# HES_Board_Rev1.net
KiCad netlist of a schematic drawn in EAGLE
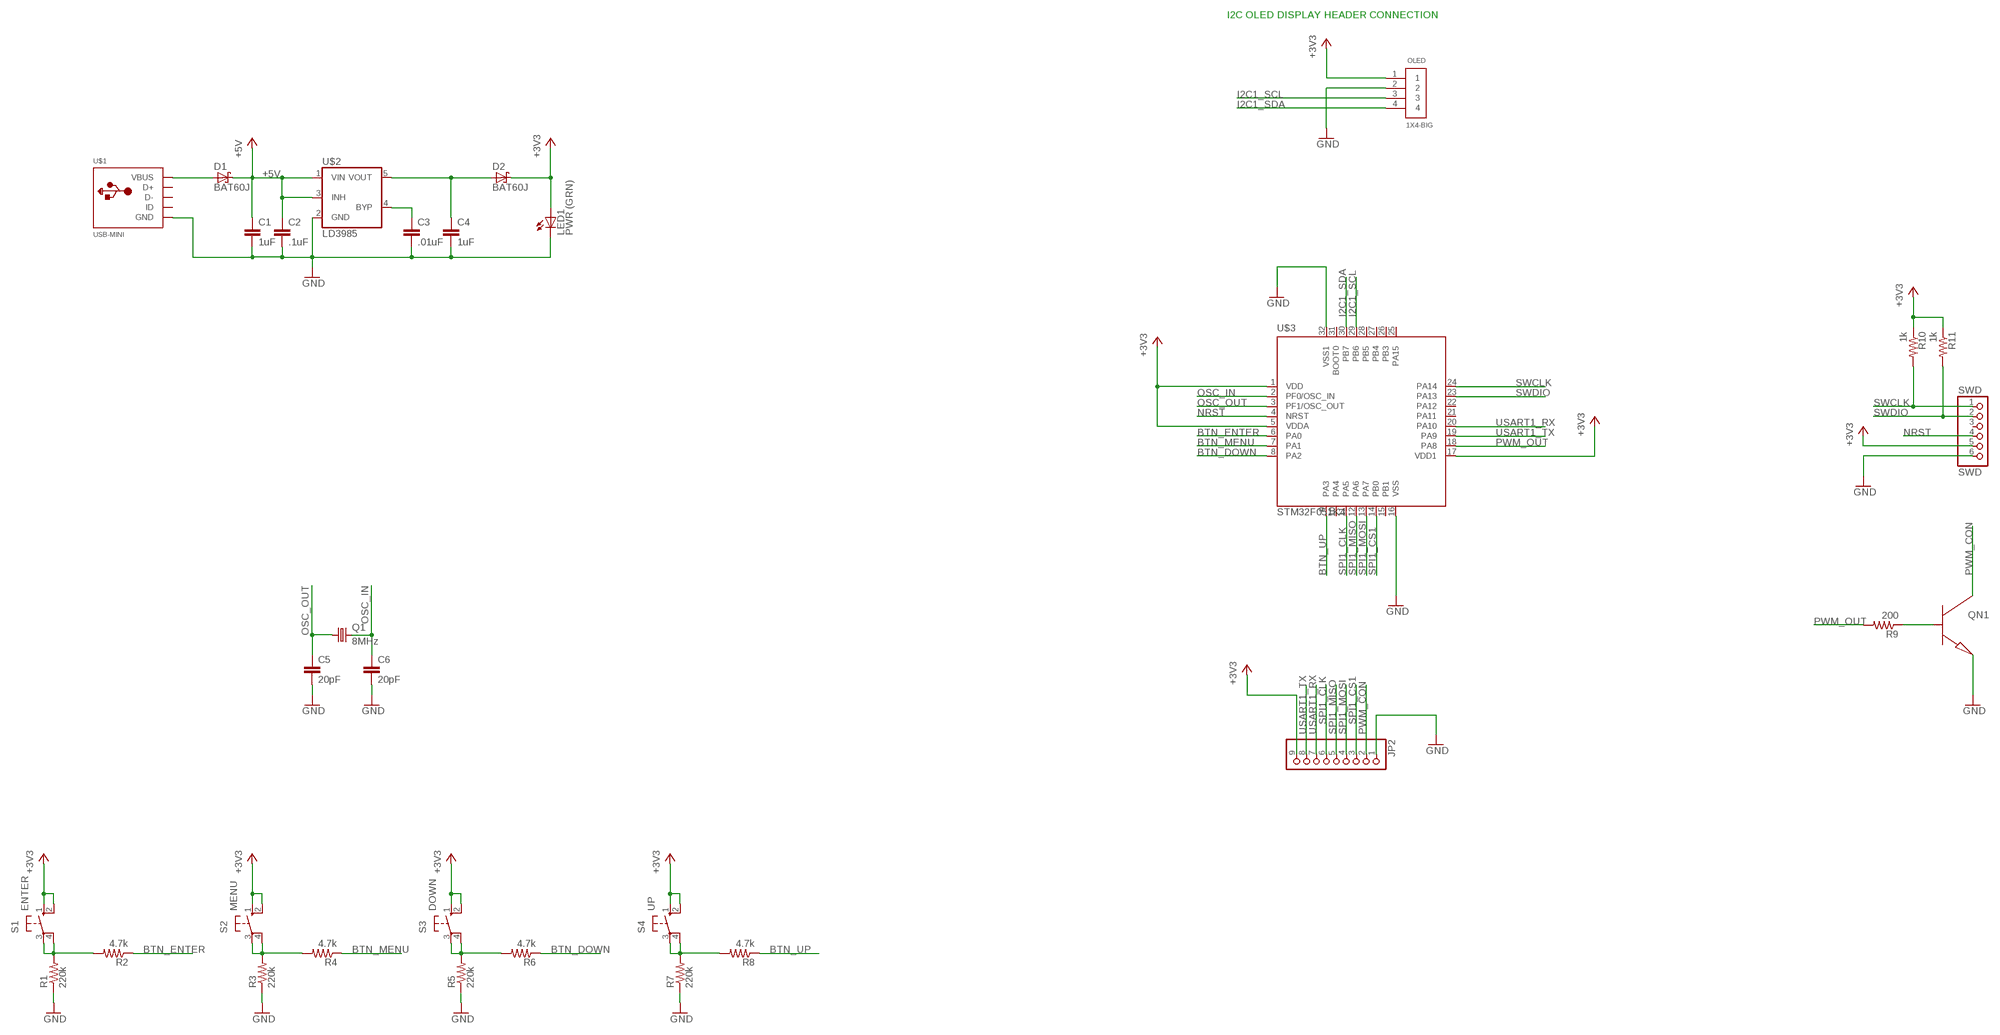
[diagram p0: schematic, sheet 1]

(export (version "E")
  (design (tool "Eeschema 10.0.6"))
  (components
    (comp (ref "C1")
      (value "1uF")
      (footprint "eagle-import:C0805")
      (libsource (lib "eagle-import") (part "C-EUC0805"))
    )
    (comp (ref "C2")
      (value ".1uF")
      (footprint "eagle-import:C0805")
      (libsource (lib "eagle-import") (part "C-EUC0805"))
    )
    (comp (ref "C3")
      (value ".01uF")
      (footprint "eagle-import:C0805")
      (libsource (lib "eagle-import") (part "C-EUC0805"))
    )
    (comp (ref "C4")
      (value "1uF")
      (footprint "eagle-import:C0805")
      (libsource (lib "eagle-import") (part "C-EUC0805"))
    )
    (comp (ref "C5")
      (value "20pF")
      (footprint "eagle-import:C0805")
      (libsource (lib "eagle-import") (part "C-EUC0805"))
    )
    (comp (ref "C6")
      (value "20pF")
      (footprint "eagle-import:C0805")
      (libsource (lib "eagle-import") (part "C-EUC0805"))
    )
    (comp (ref "D1")
      (value "BAT60J")
      (footprint "eagle-import:SOD323_ST")
      (libsource (lib "eagle-import") (part "BAT60J"))
    )
    (comp (ref "D2")
      (value "BAT60J")
      (footprint "eagle-import:SOD323_ST")
      (libsource (lib "eagle-import") (part "BAT60J"))
    )
    (comp (ref "JP2")
      (value "PINHD-1X9")
      (footprint "eagle-import:1X09-BIG")
      (libsource (lib "eagle-import") (part "PINHD-1X9"))
    )
    (comp (ref "LED1")
      (value "PWR (GRN)")
      (footprint "eagle-import:CHIP-LED0805")
      (libsource (lib "eagle-import") (part "LEDCHIP-LED0805"))
    )
    (comp (ref "OLED")
      (value "1X4-BIG")
      (footprint "eagle-import:1X04-BIG")
      (libsource (lib "eagle-import") (part "1X4-BIG"))
    )
    (comp (ref "Q1")
      (value "8MHz")
      (footprint "eagle-import:HC49_S")
      (libsource (lib "eagle-import") (part "CRYSTALHC49S"))
    )
    (comp (ref "QN1")
      (value "NPN")
      (footprint "eagle-import:SOT23")
      (libsource (lib "eagle-import") (part "NPN"))
    )
    (comp (ref "R1")
      (value "220k")
      (footprint "eagle-import:R0805")
      (libsource (lib "eagle-import") (part "R-US_R0805"))
    )
    (comp (ref "R2")
      (value "4.7k")
      (footprint "eagle-import:R0805")
      (libsource (lib "eagle-import") (part "R-US_R0805"))
    )
    (comp (ref "R3")
      (value "220k")
      (footprint "eagle-import:R0805")
      (libsource (lib "eagle-import") (part "R-US_R0805"))
    )
    (comp (ref "R4")
      (value "4.7k")
      (footprint "eagle-import:R0805")
      (libsource (lib "eagle-import") (part "R-US_R0805"))
    )
    (comp (ref "R5")
      (value "220k")
      (footprint "eagle-import:R0805")
      (libsource (lib "eagle-import") (part "R-US_R0805"))
    )
    (comp (ref "R6")
      (value "4.7k")
      (footprint "eagle-import:R0805")
      (libsource (lib "eagle-import") (part "R-US_R0805"))
    )
    (comp (ref "R7")
      (value "220k")
      (footprint "eagle-import:R0805")
      (libsource (lib "eagle-import") (part "R-US_R0805"))
    )
    (comp (ref "R8")
      (value "4.7k")
      (footprint "eagle-import:R0805")
      (libsource (lib "eagle-import") (part "R-US_R0805"))
    )
    (comp (ref "R9")
      (value "200")
      (footprint "eagle-import:R0805")
      (libsource (lib "eagle-import") (part "R-US_R0805"))
    )
    (comp (ref "R10")
      (value "1k")
      (footprint "eagle-import:R0805")
      (libsource (lib "eagle-import") (part "R-US_R0805"))
    )
    (comp (ref "R11")
      (value "1k")
      (footprint "eagle-import:R0805")
      (libsource (lib "eagle-import") (part "R-US_R0805"))
    )
    (comp (ref "S1")
      (value "ENTER")
      (footprint "eagle-import:B3F-10XX")
      (fields (field (name "MPN") "B3F-1000"))
      (libsource (lib "eagle-import") (part "10-XX"))
    )
    (comp (ref "S2")
      (value "MENU")
      (footprint "eagle-import:B3F-10XX")
      (fields (field (name "MPN") "B3F-1000"))
      (libsource (lib "eagle-import") (part "10-XX"))
    )
    (comp (ref "S3")
      (value "DOWN")
      (footprint "eagle-import:B3F-10XX")
      (fields (field (name "MPN") "B3F-1000"))
      (libsource (lib "eagle-import") (part "10-XX"))
    )
    (comp (ref "S4")
      (value "UP")
      (footprint "eagle-import:B3F-10XX")
      (fields (field (name "MPN") "B3F-1000"))
      (libsource (lib "eagle-import") (part "10-XX"))
    )
    (comp (ref "SWD")
      (value "SWD")
      (footprint "eagle-import:1X06-BIG")
      (libsource (lib "eagle-import") (part "PINHD-1X6B"))
    )
    (comp (ref "U$1")
      (value "USB-MINI")
      (footprint "eagle-import:USB-MINI")
      (libsource (lib "eagle-import") (part "USB-MINI"))
    )
    (comp (ref "U$2")
      (value "LD3985")
      (footprint "eagle-import:SOT23-5L")
      (libsource (lib "eagle-import") (part "LD3985"))
    )
    (comp (ref "U$3")
      (value "STM32F051K4")
      (footprint "eagle-import:LQFP32-7X7")
      (libsource (lib "eagle-import") (part "STM32F051K4"))
    )
  )
  (nets
    (net (code "1") (name "+3V3") (class "Default")
      (node (ref "D2") (pin "C") (pinfunction "C_C") (pintype "passive"))
      (node (ref "JP2") (pin "9") (pinfunction "9_9") (pintype "passive"))
      (node (ref "LED1") (pin "A") (pinfunction "A_A") (pintype "passive"))
      (node (ref "OLED") (pin "1") (pinfunction "1_1") (pintype "bidirectional"))
      (node (ref "R10") (pin "1") (pinfunction "1_1") (pintype "passive"))
      (node (ref "R11") (pin "1") (pinfunction "1_1") (pintype "passive"))
      (node (ref "S1") (pin "1") (pinfunction "S_1") (pintype "passive"))
      (node (ref "S1") (pin "2") (pinfunction "S1_2") (pintype "passive"))
      (node (ref "S2") (pin "1") (pinfunction "S_1") (pintype "passive"))
      (node (ref "S2") (pin "2") (pinfunction "S1_2") (pintype "passive"))
      (node (ref "S3") (pin "1") (pinfunction "S_1") (pintype "passive"))
      (node (ref "S3") (pin "2") (pinfunction "S1_2") (pintype "passive"))
      (node (ref "S4") (pin "1") (pinfunction "S_1") (pintype "passive"))
      (node (ref "S4") (pin "2") (pinfunction "S1_2") (pintype "passive"))
      (node (ref "SWD") (pin "5") (pinfunction "5_5") (pintype "passive"))
      (node (ref "U$3") (pin "1") (pinfunction "VDD_1") (pintype "power_in"))
      (node (ref "U$3") (pin "17") (pinfunction "VDD1_17") (pintype "power_in"))
      (node (ref "U$3") (pin "5") (pinfunction "VDDA_5") (pintype "power_in"))
    )
    (net (code "2") (name "+5V") (class "Default")
      (node (ref "C1") (pin "1") (pinfunction "1_1") (pintype "passive"))
      (node (ref "C2") (pin "1") (pinfunction "1_1") (pintype "passive"))
      (node (ref "D1") (pin "C") (pinfunction "C_C") (pintype "passive"))
      (node (ref "U$2") (pin "1") (pinfunction "VIN_1") (pintype "input"))
      (node (ref "U$2") (pin "3") (pinfunction "INH_3") (pintype "input"))
    )
    (net (code "3") (name "/BTN_DOWN") (class "Default")
      (node (ref "R6") (pin "1") (pinfunction "1_1") (pintype "passive"))
      (node (ref "U$3") (pin "8") (pinfunction "PA2_8") (pintype "bidirectional"))
    )
    (net (code "4") (name "/BTN_ENTER") (class "Default")
      (node (ref "R2") (pin "1") (pinfunction "1_1") (pintype "passive"))
      (node (ref "U$3") (pin "6") (pinfunction "PA0_6") (pintype "bidirectional"))
    )
    (net (code "5") (name "/BTN_MENU") (class "Default")
      (node (ref "R4") (pin "1") (pinfunction "1_1") (pintype "passive"))
      (node (ref "U$3") (pin "7") (pinfunction "PA1_7") (pintype "bidirectional"))
    )
    (net (code "6") (name "/BTN_UP") (class "Default")
      (node (ref "R8") (pin "1") (pinfunction "1_1") (pintype "passive"))
      (node (ref "U$3") (pin "9") (pinfunction "PA3_9") (pintype "bidirectional"))
    )
    (net (code "7") (name "/I2C1_SCL") (class "Default")
      (node (ref "OLED") (pin "3") (pinfunction "3_3") (pintype "bidirectional"))
      (node (ref "U$3") (pin "29") (pinfunction "PB6_29") (pintype "bidirectional"))
    )
    (net (code "8") (name "/I2C1_SDA") (class "Default")
      (node (ref "OLED") (pin "4") (pinfunction "4_4") (pintype "bidirectional"))
      (node (ref "U$3") (pin "30") (pinfunction "PB7_30") (pintype "bidirectional"))
    )
    (net (code "9") (name "/NRST") (class "Default")
      (node (ref "SWD") (pin "4") (pinfunction "4_4") (pintype "passive"))
      (node (ref "U$3") (pin "4") (pinfunction "NRST_4") (pintype "bidirectional"))
    )
    (net (code "10") (name "/OSC_IN") (class "Default")
      (node (ref "C6") (pin "1") (pinfunction "1_1") (pintype "passive"))
      (node (ref "Q1") (pin "2") (pinfunction "2_2") (pintype "passive"))
      (node (ref "U$3") (pin "2") (pinfunction "PF0/OSC_IN_2") (pintype "bidirectional"))
    )
    (net (code "11") (name "/OSC_OUT") (class "Default")
      (node (ref "C5") (pin "1") (pinfunction "1_1") (pintype "passive"))
      (node (ref "Q1") (pin "1") (pinfunction "1_1") (pintype "passive"))
      (node (ref "U$3") (pin "3") (pinfunction "PF1/OSC_OUT_3") (pintype "bidirectional"))
    )
    (net (code "12") (name "/PWM_CON") (class "Default")
      (node (ref "JP2") (pin "2") (pinfunction "2_2") (pintype "passive"))
      (node (ref "QN1") (pin "3") (pinfunction "C_3") (pintype "passive"))
    )
    (net (code "13") (name "/PWM_OUT") (class "Default")
      (node (ref "R9") (pin "2") (pinfunction "2_2") (pintype "passive"))
      (node (ref "U$3") (pin "18") (pinfunction "PA8_18") (pintype "bidirectional"))
    )
    (net (code "14") (name "/SPI1_CLK") (class "Default")
      (node (ref "JP2") (pin "6") (pinfunction "6_6") (pintype "passive"))
      (node (ref "U$3") (pin "11") (pinfunction "PA5_11") (pintype "bidirectional"))
    )
    (net (code "15") (name "/SPI1_CS1") (class "Default")
      (node (ref "JP2") (pin "3") (pinfunction "3_3") (pintype "passive"))
      (node (ref "U$3") (pin "14") (pinfunction "PB0_14") (pintype "bidirectional"))
    )
    (net (code "16") (name "/SPI1_MISO") (class "Default")
      (node (ref "JP2") (pin "5") (pinfunction "5_5") (pintype "passive"))
      (node (ref "U$3") (pin "12") (pinfunction "PA6_12") (pintype "bidirectional"))
    )
    (net (code "17") (name "/SPI1_MOSI") (class "Default")
      (node (ref "JP2") (pin "4") (pinfunction "4_4") (pintype "passive"))
      (node (ref "U$3") (pin "13") (pinfunction "PA7_13") (pintype "bidirectional"))
    )
    (net (code "18") (name "/SWCLK") (class "Default")
      (node (ref "R10") (pin "2") (pinfunction "2_2") (pintype "passive"))
      (node (ref "SWD") (pin "1") (pinfunction "1_1") (pintype "passive"))
      (node (ref "U$3") (pin "24") (pinfunction "PA14_24") (pintype "bidirectional"))
    )
    (net (code "19") (name "/SWDIO") (class "Default")
      (node (ref "R11") (pin "2") (pinfunction "2_2") (pintype "passive"))
      (node (ref "SWD") (pin "2") (pinfunction "2_2") (pintype "passive"))
      (node (ref "U$3") (pin "23") (pinfunction "PA13_23") (pintype "bidirectional"))
    )
    (net (code "20") (name "/USART1_RX") (class "Default")
      (node (ref "JP2") (pin "7") (pinfunction "7_7") (pintype "passive"))
      (node (ref "U$3") (pin "20") (pinfunction "PA10_20") (pintype "bidirectional"))
    )
    (net (code "21") (name "/USART1_TX") (class "Default")
      (node (ref "JP2") (pin "8") (pinfunction "8_8") (pintype "passive"))
      (node (ref "U$3") (pin "19") (pinfunction "PA9_19") (pintype "bidirectional"))
    )
    (net (code "22") (name "GND") (class "Default")
      (node (ref "C1") (pin "2") (pinfunction "2_2") (pintype "passive"))
      (node (ref "C2") (pin "2") (pinfunction "2_2") (pintype "passive"))
      (node (ref "C3") (pin "2") (pinfunction "2_2") (pintype "passive"))
      (node (ref "C4") (pin "2") (pinfunction "2_2") (pintype "passive"))
      (node (ref "C5") (pin "2") (pinfunction "2_2") (pintype "passive"))
      (node (ref "C6") (pin "2") (pinfunction "2_2") (pintype "passive"))
      (node (ref "JP2") (pin "1") (pinfunction "1_1") (pintype "passive"))
      (node (ref "LED1") (pin "C") (pinfunction "C_C") (pintype "passive"))
      (node (ref "OLED") (pin "2") (pinfunction "2_2") (pintype "bidirectional"))
      (node (ref "QN1") (pin "1") (pinfunction "E_1") (pintype "passive"))
      (node (ref "R1") (pin "1") (pinfunction "1_1") (pintype "passive"))
      (node (ref "R3") (pin "1") (pinfunction "1_1") (pintype "passive"))
      (node (ref "R5") (pin "1") (pinfunction "1_1") (pintype "passive"))
      (node (ref "R7") (pin "1") (pinfunction "1_1") (pintype "passive"))
      (node (ref "SWD") (pin "6") (pinfunction "6_6") (pintype "passive"))
      (node (ref "U$1") (pin "GND") (pinfunction "GND_GND") (pintype "power_in"))
      (node (ref "U$2") (pin "2") (pinfunction "GND_2") (pintype "passive"))
      (node (ref "U$3") (pin "16") (pinfunction "VSS_16") (pintype "power_in"))
      (node (ref "U$3") (pin "32") (pinfunction "VSS1_32") (pintype "power_in"))
    )
    (net (code "23") (name "Net-(D1-PadA)") (class "Default")
      (node (ref "D1") (pin "A") (pinfunction "A_A") (pintype "passive"))
      (node (ref "U$1") (pin "VBUS") (pinfunction "VBUS_VBUS") (pintype "power_in"))
    )
    (net (code "24") (name "Net-(QN1-B)") (class "Default")
      (node (ref "QN1") (pin "2") (pinfunction "B_2") (pintype "passive"))
      (node (ref "R9") (pin "1") (pinfunction "1_1") (pintype "passive"))
    )
    (net (code "25") (name "Net-(S1-P)") (class "Default")
      (node (ref "R1") (pin "2") (pinfunction "2_2") (pintype "passive"))
      (node (ref "R2") (pin "2") (pinfunction "2_2") (pintype "passive"))
      (node (ref "S1") (pin "3") (pinfunction "P_3") (pintype "passive"))
      (node (ref "S1") (pin "4") (pinfunction "P1_4") (pintype "passive"))
    )
    (net (code "26") (name "Net-(S2-P)") (class "Default")
      (node (ref "R3") (pin "2") (pinfunction "2_2") (pintype "passive"))
      (node (ref "R4") (pin "2") (pinfunction "2_2") (pintype "passive"))
      (node (ref "S2") (pin "3") (pinfunction "P_3") (pintype "passive"))
      (node (ref "S2") (pin "4") (pinfunction "P1_4") (pintype "passive"))
    )
    (net (code "27") (name "Net-(S3-P)") (class "Default")
      (node (ref "R5") (pin "2") (pinfunction "2_2") (pintype "passive"))
      (node (ref "R6") (pin "2") (pinfunction "2_2") (pintype "passive"))
      (node (ref "S3") (pin "3") (pinfunction "P_3") (pintype "passive"))
      (node (ref "S3") (pin "4") (pinfunction "P1_4") (pintype "passive"))
    )
    (net (code "28") (name "Net-(S4-P)") (class "Default")
      (node (ref "R7") (pin "2") (pinfunction "2_2") (pintype "passive"))
      (node (ref "R8") (pin "2") (pinfunction "2_2") (pintype "passive"))
      (node (ref "S4") (pin "3") (pinfunction "P_3") (pintype "passive"))
      (node (ref "S4") (pin "4") (pinfunction "P1_4") (pintype "passive"))
    )
    (net (code "29") (name "Net-(U$2-BYP)") (class "Default")
      (node (ref "C3") (pin "1") (pinfunction "1_1") (pintype "passive"))
      (node (ref "U$2") (pin "4") (pinfunction "BYP_4") (pintype "input"))
    )
    (net (code "30") (name "Net-(U$2-VOUT)") (class "Default")
      (node (ref "C4") (pin "1") (pinfunction "1_1") (pintype "passive"))
      (node (ref "D2") (pin "A") (pinfunction "A_A") (pintype "passive"))
      (node (ref "U$2") (pin "5") (pinfunction "VOUT_5") (pintype "passive"))
    )
    (net (code "31") (name "unconnected-(SWD-Pad3)") (class "Default")
      (node (ref "SWD") (pin "3") (pinfunction "3_3") (pintype "passive"))
    )
    (net (code "32") (name "unconnected-(U$1-PadD+)") (class "Default")
      (node (ref "U$1") (pin "D+") (pinfunction "D+_D+") (pintype "bidirectional"))
    )
    (net (code "33") (name "unconnected-(U$1-PadD-)") (class "Default")
      (node (ref "U$1") (pin "D-") (pinfunction "D-_D-") (pintype "bidirectional"))
    )
    (net (code "34") (name "unconnected-(U$1-PadID)") (class "Default")
      (node (ref "U$1") (pin "ID") (pinfunction "ID_ID") (pintype "bidirectional"))
    )
    (net (code "35") (name "unconnected-(U$3-BOOT0-Pad31)") (class "Default")
      (node (ref "U$3") (pin "31") (pinfunction "BOOT0_31") (pintype "bidirectional"))
    )
    (net (code "36") (name "unconnected-(U$3-PA4-Pad10)") (class "Default")
      (node (ref "U$3") (pin "10") (pinfunction "PA4_10") (pintype "bidirectional"))
    )
    (net (code "37") (name "unconnected-(U$3-PA11-Pad21)") (class "Default")
      (node (ref "U$3") (pin "21") (pinfunction "PA11_21") (pintype "bidirectional"))
    )
    (net (code "38") (name "unconnected-(U$3-PA12-Pad22)") (class "Default")
      (node (ref "U$3") (pin "22") (pinfunction "PA12_22") (pintype "bidirectional"))
    )
    (net (code "39") (name "unconnected-(U$3-PA15-Pad25)") (class "Default")
      (node (ref "U$3") (pin "25") (pinfunction "PA15_25") (pintype "bidirectional"))
    )
    (net (code "40") (name "unconnected-(U$3-PB1-Pad15)") (class "Default")
      (node (ref "U$3") (pin "15") (pinfunction "PB1_15") (pintype "bidirectional"))
    )
    (net (code "41") (name "unconnected-(U$3-PB3-Pad26)") (class "Default")
      (node (ref "U$3") (pin "26") (pinfunction "PB3_26") (pintype "bidirectional"))
    )
    (net (code "42") (name "unconnected-(U$3-PB4-Pad27)") (class "Default")
      (node (ref "U$3") (pin "27") (pinfunction "PB4_27") (pintype "bidirectional"))
    )
    (net (code "43") (name "unconnected-(U$3-PB5-Pad28)") (class "Default")
      (node (ref "U$3") (pin "28") (pinfunction "PB5_28") (pintype "bidirectional"))
    )
  )
)
